# Sheet1.net
KiCad netlist of a schematic drawn in Altium Designer
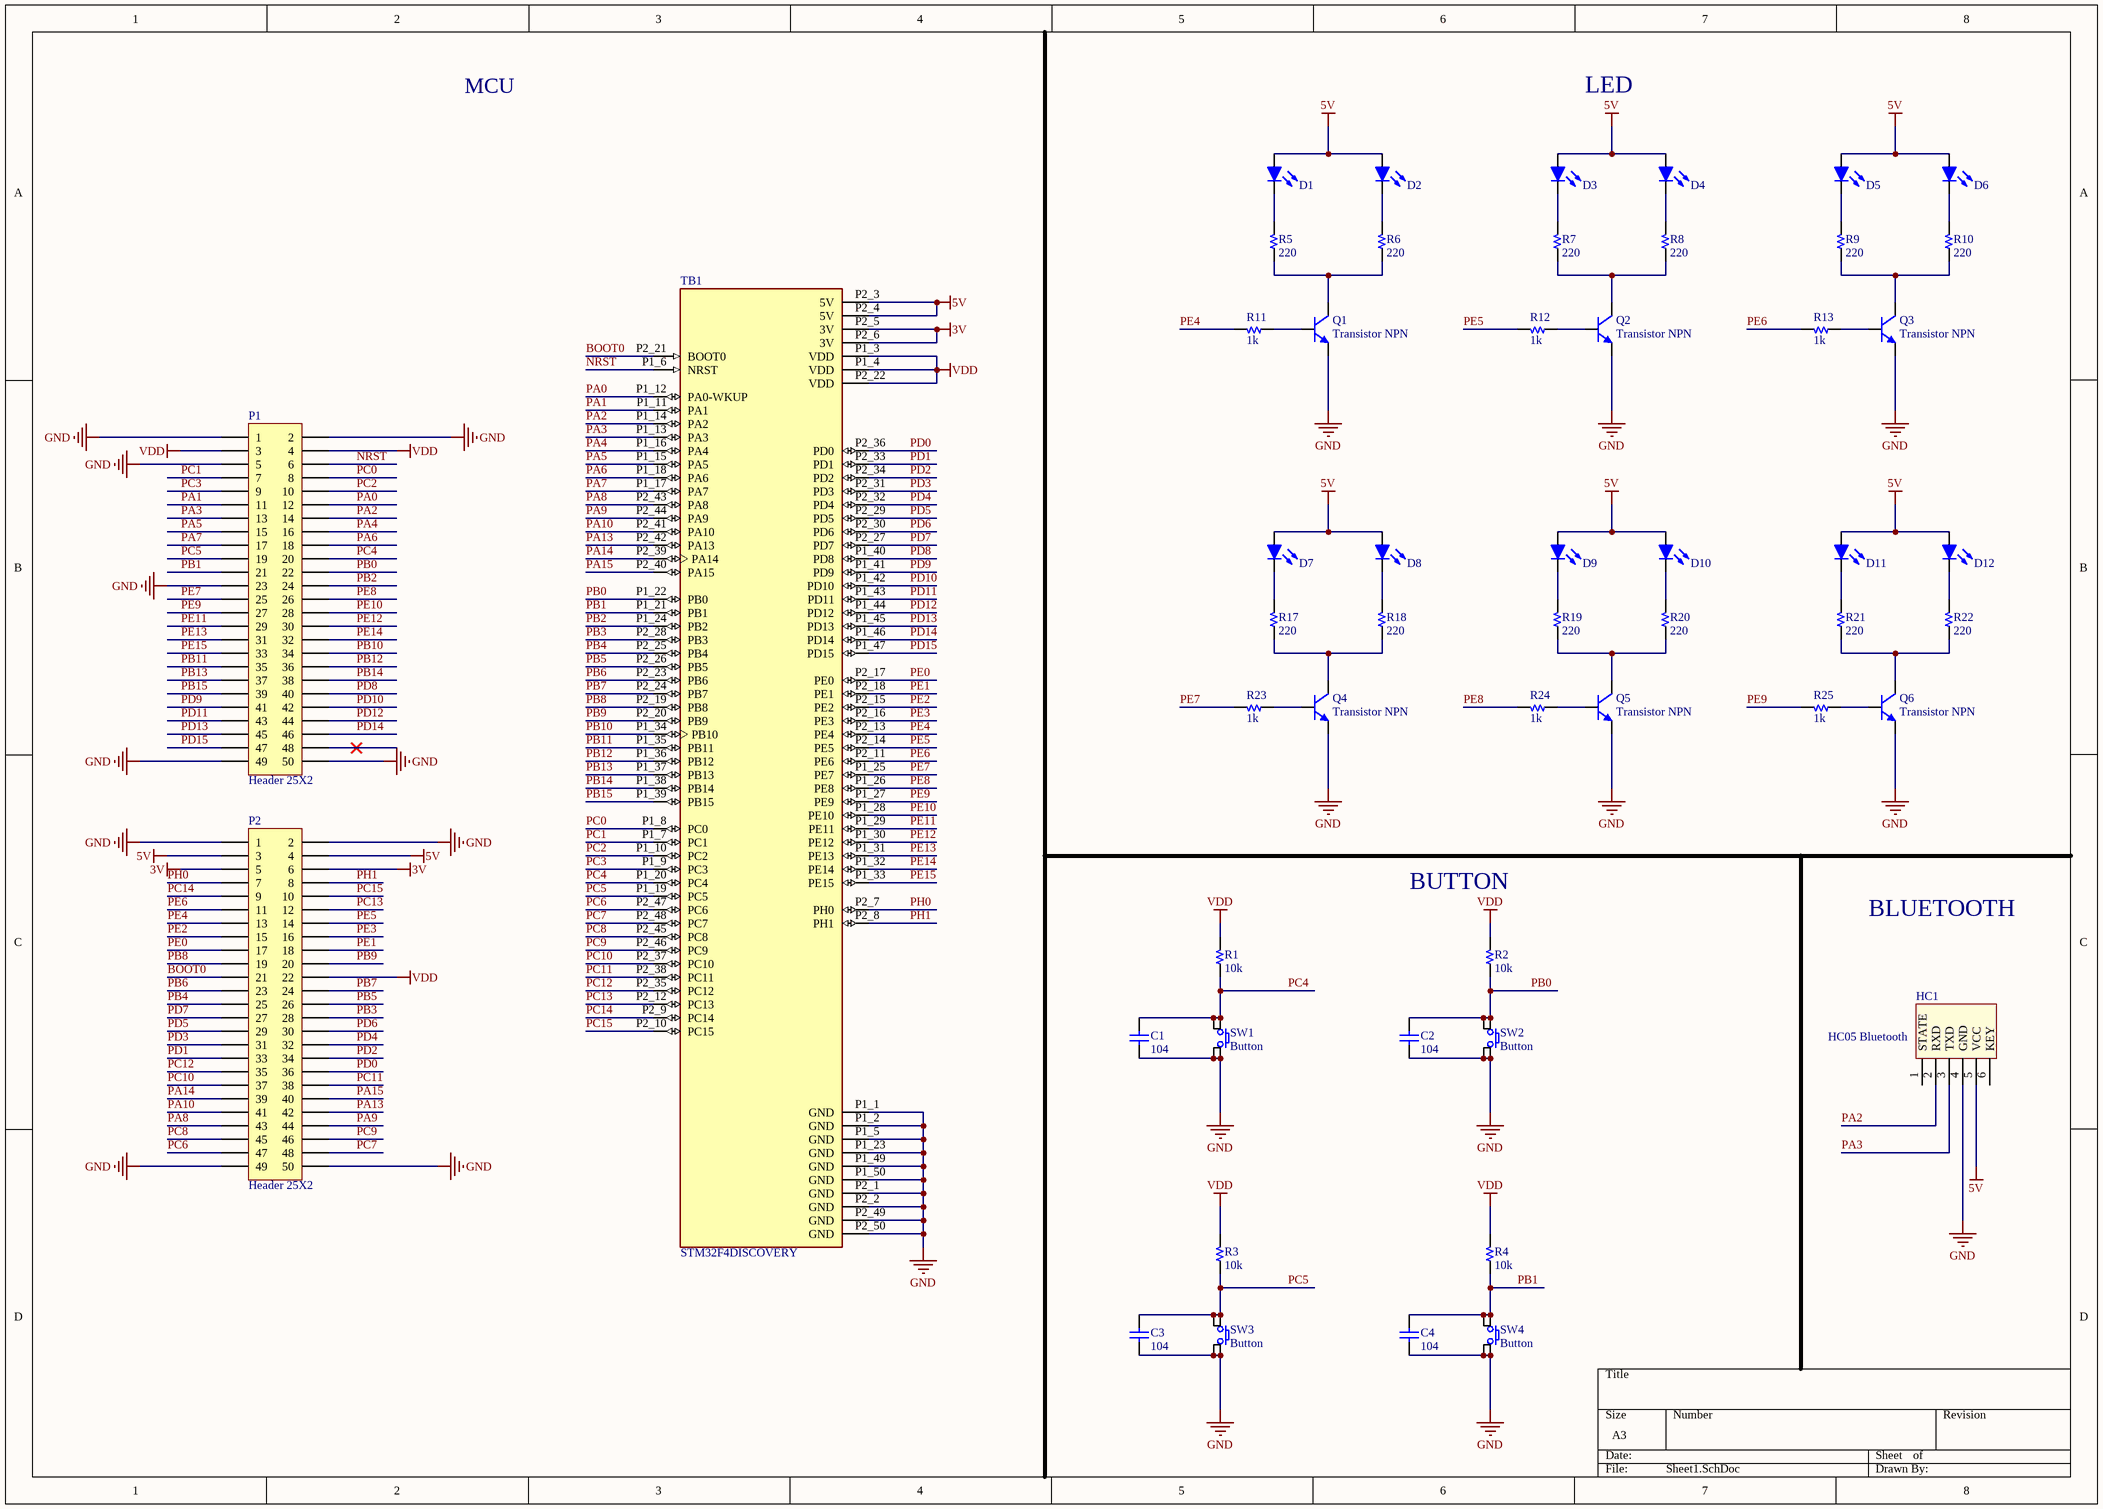
[diagram p0: Sheet1.SchDoc]

(export (version "E")
  (design (tool "Eeschema 10.0.6"))
  (components
    (comp (ref "C1")
      (value "104")
      (footprint "CAP Ceramic/W300")
      (description "Capacitor non-pol")
      (libsource (lib "chipfc_libs") (part "Capacitor NP"))
    )
    (comp (ref "C2")
      (value "104")
      (footprint "CAP Ceramic/W300")
      (description "Capacitor non-pol")
      (libsource (lib "chipfc_libs") (part "Capacitor NP"))
    )
    (comp (ref "C3")
      (value "104")
      (footprint "CAP Ceramic/W300")
      (description "Capacitor non-pol")
      (libsource (lib "chipfc_libs") (part "Capacitor NP"))
    )
    (comp (ref "C4")
      (value "104")
      (footprint "CAP Ceramic/W300")
      (description "Capacitor non-pol")
      (libsource (lib "chipfc_libs") (part "Capacitor NP"))
    )
    (comp (ref "D1")
      (value "Led")
      (footprint "LED 3MM - green")
      (description "Typical LED")
      (libsource (lib "led") (part "Led"))
    )
    (comp (ref "D2")
      (value "Led")
      (footprint "LED 3MM - green")
      (description "Typical LED")
      (libsource (lib "led") (part "Led"))
    )
    (comp (ref "D3")
      (value "Led")
      (footprint "LED 3MM - yellow")
      (description "Typical LED")
      (libsource (lib "led") (part "Led"))
    )
    (comp (ref "D4")
      (value "Led")
      (footprint "LED 3MM - yellow")
      (description "Typical LED")
      (libsource (lib "led") (part "Led"))
    )
    (comp (ref "D5")
      (value "Led")
      (footprint "LED 3MM - red")
      (description "Typical LED")
      (libsource (lib "led") (part "Led"))
    )
    (comp (ref "D6")
      (value "Led")
      (footprint "LED 3MM - red")
      (description "Typical LED")
      (libsource (lib "led") (part "Led"))
    )
    (comp (ref "D7")
      (value "Led")
      (footprint "LED 3MM - green")
      (description "Typical LED")
      (libsource (lib "led") (part "Led"))
    )
    (comp (ref "D8")
      (value "Led")
      (footprint "LED 3MM - green")
      (description "Typical LED")
      (libsource (lib "led") (part "Led"))
    )
    (comp (ref "D9")
      (value "Led")
      (footprint "LED 3MM - yellow")
      (description "Typical LED")
      (libsource (lib "led") (part "Led"))
    )
    (comp (ref "D10")
      (value "Led")
      (footprint "LED 3MM - yellow")
      (description "Typical LED")
      (libsource (lib "led") (part "Led"))
    )
    (comp (ref "D11")
      (value "Led")
      (footprint "LED 3MM - red")
      (description "Typical LED")
      (libsource (lib "led") (part "Led"))
    )
    (comp (ref "D12")
      (value "Led")
      (footprint "LED 3MM - red")
      (description "Typical LED")
      (libsource (lib "led") (part "Led"))
    )
    (comp (ref "HC1")
      (value "HC05 Bluetooth")
      (footprint "HC05 Bluethooth Dung")
      (description "Bluetooth HC05")
      (libsource (lib "Altium_Lib_by_KhueNguyenCreator") (part "HC05 Bluetooth"))
    )
    (comp (ref "P1")
      (value "Header 25X2")
      (footprint "HDR2X25")
      (description "Header, 25-Pin, Dual row")
      (fields (field (name "PUBLISHER") "Altium Limited"))
      (libsource (lib "Miscellaneous Connectors") (part "Header 25X2"))
    )
    (comp (ref "P2")
      (value "Header 25X2")
      (footprint "HDR2X25")
      (description "Header, 25-Pin, Dual row")
      (fields (field (name "PUBLISHER") "Altium Limited"))
      (libsource (lib "Miscellaneous Connectors") (part "Header 25X2"))
    )
    (comp (ref "Q1")
      (value "Transistor NPN")
      (footprint "TO-92/W100")
      (description "NPN Bipolar Transistor")
      (libsource (lib "chipfc_libs") (part "Transistor NPN"))
    )
    (comp (ref "Q2")
      (value "Transistor NPN")
      (footprint "TO-92/W100")
      (description "NPN Bipolar Transistor")
      (libsource (lib "chipfc_libs") (part "Transistor NPN"))
    )
    (comp (ref "Q3")
      (value "Transistor NPN")
      (footprint "TO-92/W100")
      (description "NPN Bipolar Transistor")
      (libsource (lib "chipfc_libs") (part "Transistor NPN"))
    )
    (comp (ref "Q4")
      (value "Transistor NPN")
      (footprint "TO-92/W100")
      (description "NPN Bipolar Transistor")
      (libsource (lib "chipfc_libs") (part "Transistor NPN"))
    )
    (comp (ref "Q5")
      (value "Transistor NPN")
      (footprint "TO-92/W100")
      (description "NPN Bipolar Transistor")
      (libsource (lib "chipfc_libs") (part "Transistor NPN"))
    )
    (comp (ref "Q6")
      (value "Transistor NPN")
      (footprint "TO-92/W100")
      (description "NPN Bipolar Transistor")
      (libsource (lib "chipfc_libs") (part "Transistor NPN"))
    )
    (comp (ref "R1")
      (value "10k")
      (footprint "R 1/4W/300")
      (description "Resistor")
      (libsource (lib "chipfc_libs") (part "Resistor"))
    )
    (comp (ref "R2")
      (value "10k")
      (footprint "R 1/4W/300")
      (description "Resistor")
      (libsource (lib "chipfc_libs") (part "Resistor"))
    )
    (comp (ref "R3")
      (value "10k")
      (footprint "R 1/4W/300")
      (description "Resistor")
      (libsource (lib "chipfc_libs") (part "Resistor"))
    )
    (comp (ref "R4")
      (value "10k")
      (footprint "R 1/4W/300")
      (description "Resistor")
      (libsource (lib "chipfc_libs") (part "Resistor"))
    )
    (comp (ref "R5")
      (value "220")
      (footprint "R 1/4W/300")
      (description "Resistor")
      (libsource (lib "chipfc_libs") (part "Resistor"))
    )
    (comp (ref "R6")
      (value "220")
      (footprint "R 1/4W/300")
      (description "Resistor")
      (libsource (lib "chipfc_libs") (part "Resistor"))
    )
    (comp (ref "R7")
      (value "220")
      (footprint "R 1/4W/300")
      (description "Resistor")
      (libsource (lib "chipfc_libs") (part "Resistor"))
    )
    (comp (ref "R8")
      (value "220")
      (footprint "R 1/4W/300")
      (description "Resistor")
      (libsource (lib "chipfc_libs") (part "Resistor"))
    )
    (comp (ref "R9")
      (value "220")
      (footprint "R 1/4W/300")
      (description "Resistor")
      (libsource (lib "chipfc_libs") (part "Resistor"))
    )
    (comp (ref "R10")
      (value "220")
      (footprint "R 1/4W/300")
      (description "Resistor")
      (libsource (lib "chipfc_libs") (part "Resistor"))
    )
    (comp (ref "R11")
      (value "1k")
      (footprint "R 1/4W/300")
      (description "Resistor")
      (libsource (lib "chipfc_libs") (part "Resistor"))
    )
    (comp (ref "R12")
      (value "1k")
      (footprint "R 1/4W/300")
      (description "Resistor")
      (libsource (lib "chipfc_libs") (part "Resistor"))
    )
    (comp (ref "R13")
      (value "1k")
      (footprint "R 1/4W/300")
      (description "Resistor")
      (libsource (lib "chipfc_libs") (part "Resistor"))
    )
    (comp (ref "R17")
      (value "220")
      (footprint "R 1/4W/300")
      (description "Resistor")
      (libsource (lib "chipfc_libs") (part "Resistor"))
    )
    (comp (ref "R18")
      (value "220")
      (footprint "R 1/4W/300")
      (description "Resistor")
      (libsource (lib "chipfc_libs") (part "Resistor"))
    )
    (comp (ref "R19")
      (value "220")
      (footprint "R 1/4W/300")
      (description "Resistor")
      (libsource (lib "chipfc_libs") (part "Resistor"))
    )
    (comp (ref "R20")
      (value "220")
      (footprint "R 1/4W/300")
      (description "Resistor")
      (libsource (lib "chipfc_libs") (part "Resistor"))
    )
    (comp (ref "R21")
      (value "220")
      (footprint "R 1/4W/300")
      (description "Resistor")
      (libsource (lib "chipfc_libs") (part "Resistor"))
    )
    (comp (ref "R22")
      (value "220")
      (footprint "R 1/4W/300")
      (description "Resistor")
      (libsource (lib "chipfc_libs") (part "Resistor"))
    )
    (comp (ref "R23")
      (value "1k")
      (footprint "R 1/4W/300")
      (description "Resistor")
      (libsource (lib "chipfc_libs") (part "Resistor"))
    )
    (comp (ref "R24")
      (value "1k")
      (footprint "R 1/4W/300")
      (description "Resistor")
      (libsource (lib "chipfc_libs") (part "Resistor"))
    )
    (comp (ref "R25")
      (value "1k")
      (footprint "R 1/4W/300")
      (description "Resistor")
      (libsource (lib "chipfc_libs") (part "Resistor"))
    )
    (comp (ref "SW1")
      (value "Button")
      (footprint "SW/4/12mm")
      (description "Tact switch 4-pin")
      (libsource (lib "bs_libs") (part "SW SPST 4-pin"))
    )
    (comp (ref "SW2")
      (value "Button")
      (footprint "SW/4/12mm")
      (description "Tact switch 4-pin")
      (libsource (lib "bs_libs") (part "SW SPST 4-pin"))
    )
    (comp (ref "SW3")
      (value "Button")
      (footprint "SW/4/12mm")
      (description "Tact switch 4-pin")
      (libsource (lib "bs_libs") (part "SW SPST 4-pin"))
    )
    (comp (ref "SW4")
      (value "Button")
      (footprint "SW/4/12mm")
      (description "Tact switch 4-pin")
      (libsource (lib "bs_libs") (part "SW SPST 4-pin"))
    )
    (comp (ref "TB1")
      (value "STM32F4DISCOVERY")
      (footprint "MODULE_STM32F4DISCOVERY")
      (description "Development kit: ARM ST; pin strips, pin header; No.of")
      (libsource (lib "STM32F4DISCOVERY") (part "STM32F4DISCOVERY"))
    )
  )
  (nets
    (net (code "1") (name "/BOOT0") (class "Default")
      (node (ref "P2") (pin "21") (pinfunction "21_21") (pintype "passive"))
      (node (ref "TB1") (pin "P2_21") (pinfunction "BOOT0_P2_21") (pintype "input"))
    )
    (net (code "2") (name "/NRST") (class "Default")
      (node (ref "P1") (pin "6") (pinfunction "6_6") (pintype "passive"))
      (node (ref "TB1") (pin "P1_6") (pinfunction "NRST_P1_6") (pintype "input"))
    )
    (net (code "3") (name "/PA0") (class "Default")
      (node (ref "P1") (pin "12") (pinfunction "12_12") (pintype "passive"))
      (node (ref "TB1") (pin "P1_12") (pinfunction "PA0-WKUP_P1_12") (pintype "bidirectional"))
    )
    (net (code "4") (name "/PA1") (class "Default")
      (node (ref "P1") (pin "11") (pinfunction "11_11") (pintype "passive"))
      (node (ref "TB1") (pin "P1_11") (pinfunction "PA1_P1_11") (pintype "bidirectional"))
    )
    (net (code "5") (name "/PA2") (class "Default")
      (node (ref "HC1") (pin "2") (pinfunction "RXD_2") (pintype "passive"))
      (node (ref "P1") (pin "14") (pinfunction "14_14") (pintype "passive"))
      (node (ref "TB1") (pin "P1_14") (pinfunction "PA2_P1_14") (pintype "bidirectional"))
    )
    (net (code "6") (name "/PA3") (class "Default")
      (node (ref "HC1") (pin "3") (pinfunction "TXD_3") (pintype "passive"))
      (node (ref "P1") (pin "13") (pinfunction "13_13") (pintype "passive"))
      (node (ref "TB1") (pin "P1_13") (pinfunction "PA3_P1_13") (pintype "bidirectional"))
    )
    (net (code "7") (name "/PA4") (class "Default")
      (node (ref "P1") (pin "16") (pinfunction "16_16") (pintype "passive"))
      (node (ref "TB1") (pin "P1_16") (pinfunction "PA4_P1_16") (pintype "bidirectional"))
    )
    (net (code "8") (name "/PA5") (class "Default")
      (node (ref "P1") (pin "15") (pinfunction "15_15") (pintype "passive"))
      (node (ref "TB1") (pin "P1_15") (pinfunction "PA5_P1_15") (pintype "bidirectional"))
    )
    (net (code "9") (name "/PA6") (class "Default")
      (node (ref "P1") (pin "18") (pinfunction "18_18") (pintype "passive"))
      (node (ref "TB1") (pin "P1_18") (pinfunction "PA6_P1_18") (pintype "bidirectional"))
    )
    (net (code "10") (name "/PA7") (class "Default")
      (node (ref "P1") (pin "17") (pinfunction "17_17") (pintype "passive"))
      (node (ref "TB1") (pin "P1_17") (pinfunction "PA7_P1_17") (pintype "bidirectional"))
    )
    (net (code "11") (name "/PA8") (class "Default")
      (node (ref "P2") (pin "43") (pinfunction "43_43") (pintype "passive"))
      (node (ref "TB1") (pin "P2_43") (pinfunction "PA8_P2_43") (pintype "bidirectional"))
    )
    (net (code "12") (name "/PA9") (class "Default")
      (node (ref "P2") (pin "44") (pinfunction "44_44") (pintype "passive"))
      (node (ref "TB1") (pin "P2_44") (pinfunction "PA9_P2_44") (pintype "bidirectional"))
    )
    (net (code "13") (name "/PA10") (class "Default")
      (node (ref "P2") (pin "41") (pinfunction "41_41") (pintype "passive"))
      (node (ref "TB1") (pin "P2_41") (pinfunction "PA10_P2_41") (pintype "bidirectional"))
    )
    (net (code "14") (name "/PA13") (class "Default")
      (node (ref "P2") (pin "42") (pinfunction "42_42") (pintype "passive"))
      (node (ref "TB1") (pin "P2_42") (pinfunction "PA13_P2_42") (pintype "bidirectional"))
    )
    (net (code "15") (name "/PA14") (class "Default")
      (node (ref "P2") (pin "39") (pinfunction "39_39") (pintype "passive"))
      (node (ref "TB1") (pin "P2_39") (pinfunction "PA14_P2_39") (pintype "bidirectional"))
    )
    (net (code "16") (name "/PA15") (class "Default")
      (node (ref "P2") (pin "40") (pinfunction "40_40") (pintype "passive"))
      (node (ref "TB1") (pin "P2_40") (pinfunction "PA15_P2_40") (pintype "bidirectional"))
    )
    (net (code "17") (name "/PB0") (class "Default")
      (node (ref "C2") (pin "1") (pinfunction "1_1") (pintype "passive"))
      (node (ref "P1") (pin "22") (pinfunction "22_22") (pintype "passive"))
      (node (ref "R2") (pin "1") (pinfunction "1_1") (pintype "passive"))
      (node (ref "SW2") (pin "1") (pinfunction "1_1") (pintype "passive"))
      (node (ref "SW2") (pin "2") (pinfunction "2_2") (pintype "passive"))
      (node (ref "TB1") (pin "P1_22") (pinfunction "PB0_P1_22") (pintype "bidirectional"))
    )
    (net (code "18") (name "/PB1") (class "Default")
      (node (ref "C4") (pin "1") (pinfunction "1_1") (pintype "passive"))
      (node (ref "P1") (pin "21") (pinfunction "21_21") (pintype "passive"))
      (node (ref "R4") (pin "1") (pinfunction "1_1") (pintype "passive"))
      (node (ref "SW4") (pin "1") (pinfunction "1_1") (pintype "passive"))
      (node (ref "SW4") (pin "2") (pinfunction "2_2") (pintype "passive"))
      (node (ref "TB1") (pin "P1_21") (pinfunction "PB1_P1_21") (pintype "bidirectional"))
    )
    (net (code "19") (name "/PB2") (class "Default")
      (node (ref "P1") (pin "24") (pinfunction "24_24") (pintype "passive"))
      (node (ref "TB1") (pin "P1_24") (pinfunction "PB2_P1_24") (pintype "bidirectional"))
    )
    (net (code "20") (name "/PB3") (class "Default")
      (node (ref "P2") (pin "28") (pinfunction "28_28") (pintype "passive"))
      (node (ref "TB1") (pin "P2_28") (pinfunction "PB3_P2_28") (pintype "bidirectional"))
    )
    (net (code "21") (name "/PB4") (class "Default")
      (node (ref "P2") (pin "25") (pinfunction "25_25") (pintype "passive"))
      (node (ref "TB1") (pin "P2_25") (pinfunction "PB4_P2_25") (pintype "bidirectional"))
    )
    (net (code "22") (name "/PB5") (class "Default")
      (node (ref "P2") (pin "26") (pinfunction "26_26") (pintype "passive"))
      (node (ref "TB1") (pin "P2_26") (pinfunction "PB5_P2_26") (pintype "bidirectional"))
    )
    (net (code "23") (name "/PB6") (class "Default")
      (node (ref "P2") (pin "23") (pinfunction "23_23") (pintype "passive"))
      (node (ref "TB1") (pin "P2_23") (pinfunction "PB6_P2_23") (pintype "bidirectional"))
    )
    (net (code "24") (name "/PB7") (class "Default")
      (node (ref "P2") (pin "24") (pinfunction "24_24") (pintype "passive"))
      (node (ref "TB1") (pin "P2_24") (pinfunction "PB7_P2_24") (pintype "bidirectional"))
    )
    (net (code "25") (name "/PB8") (class "Default")
      (node (ref "P2") (pin "19") (pinfunction "19_19") (pintype "passive"))
      (node (ref "TB1") (pin "P2_19") (pinfunction "PB8_P2_19") (pintype "bidirectional"))
    )
    (net (code "26") (name "/PB9") (class "Default")
      (node (ref "P2") (pin "20") (pinfunction "20_20") (pintype "passive"))
      (node (ref "TB1") (pin "P2_20") (pinfunction "PB9_P2_20") (pintype "bidirectional"))
    )
    (net (code "27") (name "/PB10") (class "Default")
      (node (ref "P1") (pin "34") (pinfunction "34_34") (pintype "passive"))
      (node (ref "TB1") (pin "P1_34") (pinfunction "PB10_P1_34") (pintype "bidirectional"))
    )
    (net (code "28") (name "/PB11") (class "Default")
      (node (ref "P1") (pin "35") (pinfunction "35_35") (pintype "passive"))
      (node (ref "TB1") (pin "P1_35") (pinfunction "PB11_P1_35") (pintype "bidirectional"))
    )
    (net (code "29") (name "/PB12") (class "Default")
      (node (ref "P1") (pin "36") (pinfunction "36_36") (pintype "passive"))
      (node (ref "TB1") (pin "P1_36") (pinfunction "PB12_P1_36") (pintype "bidirectional"))
    )
    (net (code "30") (name "/PB13") (class "Default")
      (node (ref "P1") (pin "37") (pinfunction "37_37") (pintype "passive"))
      (node (ref "TB1") (pin "P1_37") (pinfunction "PB13_P1_37") (pintype "bidirectional"))
    )
    (net (code "31") (name "/PB14") (class "Default")
      (node (ref "P1") (pin "38") (pinfunction "38_38") (pintype "passive"))
      (node (ref "TB1") (pin "P1_38") (pinfunction "PB14_P1_38") (pintype "bidirectional"))
    )
    (net (code "32") (name "/PB15") (class "Default")
      (node (ref "P1") (pin "39") (pinfunction "39_39") (pintype "passive"))
      (node (ref "TB1") (pin "P1_39") (pinfunction "PB15_P1_39") (pintype "bidirectional"))
    )
    (net (code "33") (name "/PC0") (class "Default")
      (node (ref "P1") (pin "8") (pinfunction "8_8") (pintype "passive"))
      (node (ref "TB1") (pin "P1_8") (pinfunction "PC0_P1_8") (pintype "bidirectional"))
    )
    (net (code "34") (name "/PC1") (class "Default")
      (node (ref "P1") (pin "7") (pinfunction "7_7") (pintype "passive"))
      (node (ref "TB1") (pin "P1_7") (pinfunction "PC1_P1_7") (pintype "bidirectional"))
    )
    (net (code "35") (name "/PC2") (class "Default")
      (node (ref "P1") (pin "10") (pinfunction "10_10") (pintype "passive"))
      (node (ref "TB1") (pin "P1_10") (pinfunction "PC2_P1_10") (pintype "bidirectional"))
    )
    (net (code "36") (name "/PC3") (class "Default")
      (node (ref "P1") (pin "9") (pinfunction "9_9") (pintype "passive"))
      (node (ref "TB1") (pin "P1_9") (pinfunction "PC3_P1_9") (pintype "bidirectional"))
    )
    (net (code "37") (name "/PC4") (class "Default")
      (node (ref "C1") (pin "1") (pinfunction "1_1") (pintype "passive"))
      (node (ref "P1") (pin "20") (pinfunction "20_20") (pintype "passive"))
      (node (ref "R1") (pin "1") (pinfunction "1_1") (pintype "passive"))
      (node (ref "SW1") (pin "1") (pinfunction "1_1") (pintype "passive"))
      (node (ref "SW1") (pin "2") (pinfunction "2_2") (pintype "passive"))
      (node (ref "TB1") (pin "P1_20") (pinfunction "PC4_P1_20") (pintype "bidirectional"))
    )
    (net (code "38") (name "/PC5") (class "Default")
      (node (ref "C3") (pin "1") (pinfunction "1_1") (pintype "passive"))
      (node (ref "P1") (pin "19") (pinfunction "19_19") (pintype "passive"))
      (node (ref "R3") (pin "1") (pinfunction "1_1") (pintype "passive"))
      (node (ref "SW3") (pin "1") (pinfunction "1_1") (pintype "passive"))
      (node (ref "SW3") (pin "2") (pinfunction "2_2") (pintype "passive"))
      (node (ref "TB1") (pin "P1_19") (pinfunction "PC5_P1_19") (pintype "bidirectional"))
    )
    (net (code "39") (name "/PC6") (class "Default")
      (node (ref "P2") (pin "47") (pinfunction "47_47") (pintype "passive"))
      (node (ref "TB1") (pin "P2_47") (pinfunction "PC6_P2_47") (pintype "bidirectional"))
    )
    (net (code "40") (name "/PC7") (class "Default")
      (node (ref "P2") (pin "48") (pinfunction "48_48") (pintype "passive"))
      (node (ref "TB1") (pin "P2_48") (pinfunction "PC7_P2_48") (pintype "bidirectional"))
    )
    (net (code "41") (name "/PC8") (class "Default")
      (node (ref "P2") (pin "45") (pinfunction "45_45") (pintype "passive"))
      (node (ref "TB1") (pin "P2_45") (pinfunction "PC8_P2_45") (pintype "bidirectional"))
    )
    (net (code "42") (name "/PC9") (class "Default")
      (node (ref "P2") (pin "46") (pinfunction "46_46") (pintype "passive"))
      (node (ref "TB1") (pin "P2_46") (pinfunction "PC9_P2_46") (pintype "bidirectional"))
    )
    (net (code "43") (name "/PC10") (class "Default")
      (node (ref "P2") (pin "37") (pinfunction "37_37") (pintype "passive"))
      (node (ref "TB1") (pin "P2_37") (pinfunction "PC10_P2_37") (pintype "bidirectional"))
    )
    (net (code "44") (name "/PC11") (class "Default")
      (node (ref "P2") (pin "38") (pinfunction "38_38") (pintype "passive"))
      (node (ref "TB1") (pin "P2_38") (pinfunction "PC11_P2_38") (pintype "bidirectional"))
    )
    (net (code "45") (name "/PC12") (class "Default")
      (node (ref "P2") (pin "35") (pinfunction "35_35") (pintype "passive"))
      (node (ref "TB1") (pin "P2_35") (pinfunction "PC12_P2_35") (pintype "bidirectional"))
    )
    (net (code "46") (name "/PC13") (class "Default")
      (node (ref "P2") (pin "12") (pinfunction "12_12") (pintype "passive"))
      (node (ref "TB1") (pin "P2_12") (pinfunction "PC13_P2_12") (pintype "bidirectional"))
    )
    (net (code "47") (name "/PC14") (class "Default")
      (node (ref "P2") (pin "9") (pinfunction "9_9") (pintype "passive"))
      (node (ref "TB1") (pin "P2_9") (pinfunction "PC14_P2_9") (pintype "bidirectional"))
    )
    (net (code "48") (name "/PC15") (class "Default")
      (node (ref "P2") (pin "10") (pinfunction "10_10") (pintype "passive"))
      (node (ref "TB1") (pin "P2_10") (pinfunction "PC15_P2_10") (pintype "bidirectional"))
    )
    (net (code "49") (name "/PD0") (class "Default")
      (node (ref "P2") (pin "36") (pinfunction "36_36") (pintype "passive"))
      (node (ref "TB1") (pin "P2_36") (pinfunction "PD0_P2_36") (pintype "bidirectional"))
    )
    (net (code "50") (name "/PD1") (class "Default")
      (node (ref "P2") (pin "33") (pinfunction "33_33") (pintype "passive"))
      (node (ref "TB1") (pin "P2_33") (pinfunction "PD1_P2_33") (pintype "bidirectional"))
    )
    (net (code "51") (name "/PD2") (class "Default")
      (node (ref "P2") (pin "34") (pinfunction "34_34") (pintype "passive"))
      (node (ref "TB1") (pin "P2_34") (pinfunction "PD2_P2_34") (pintype "bidirectional"))
    )
    (net (code "52") (name "/PD3") (class "Default")
      (node (ref "P2") (pin "31") (pinfunction "31_31") (pintype "passive"))
      (node (ref "TB1") (pin "P2_31") (pinfunction "PD3_P2_31") (pintype "bidirectional"))
    )
    (net (code "53") (name "/PD4") (class "Default")
      (node (ref "P2") (pin "32") (pinfunction "32_32") (pintype "passive"))
      (node (ref "TB1") (pin "P2_32") (pinfunction "PD4_P2_32") (pintype "bidirectional"))
    )
    (net (code "54") (name "/PD5") (class "Default")
      (node (ref "P2") (pin "29") (pinfunction "29_29") (pintype "passive"))
      (node (ref "TB1") (pin "P2_29") (pinfunction "PD5_P2_29") (pintype "bidirectional"))
    )
    (net (code "55") (name "/PD6") (class "Default")
      (node (ref "P2") (pin "30") (pinfunction "30_30") (pintype "passive"))
      (node (ref "TB1") (pin "P2_30") (pinfunction "PD6_P2_30") (pintype "bidirectional"))
    )
    (net (code "56") (name "/PD7") (class "Default")
      (node (ref "P2") (pin "27") (pinfunction "27_27") (pintype "passive"))
      (node (ref "TB1") (pin "P2_27") (pinfunction "PD7_P2_27") (pintype "bidirectional"))
    )
    (net (code "57") (name "/PD8") (class "Default")
      (node (ref "P1") (pin "40") (pinfunction "40_40") (pintype "passive"))
      (node (ref "TB1") (pin "P1_40") (pinfunction "PD8_P1_40") (pintype "bidirectional"))
    )
    (net (code "58") (name "/PD9") (class "Default")
      (node (ref "P1") (pin "41") (pinfunction "41_41") (pintype "passive"))
      (node (ref "TB1") (pin "P1_41") (pinfunction "PD9_P1_41") (pintype "bidirectional"))
    )
    (net (code "59") (name "/PD10") (class "Default")
      (node (ref "P1") (pin "42") (pinfunction "42_42") (pintype "passive"))
      (node (ref "TB1") (pin "P1_42") (pinfunction "PD10_P1_42") (pintype "bidirectional"))
    )
    (net (code "60") (name "/PD11") (class "Default")
      (node (ref "P1") (pin "43") (pinfunction "43_43") (pintype "passive"))
      (node (ref "TB1") (pin "P1_43") (pinfunction "PD11_P1_43") (pintype "bidirectional"))
    )
    (net (code "61") (name "/PD12") (class "Default")
      (node (ref "P1") (pin "44") (pinfunction "44_44") (pintype "passive"))
      (node (ref "TB1") (pin "P1_44") (pinfunction "PD12_P1_44") (pintype "bidirectional"))
    )
    (net (code "62") (name "/PD13") (class "Default")
      (node (ref "P1") (pin "45") (pinfunction "45_45") (pintype "passive"))
      (node (ref "TB1") (pin "P1_45") (pinfunction "PD13_P1_45") (pintype "bidirectional"))
    )
    (net (code "63") (name "/PD14") (class "Default")
      (node (ref "P1") (pin "46") (pinfunction "46_46") (pintype "passive"))
      (node (ref "TB1") (pin "P1_46") (pinfunction "PD14_P1_46") (pintype "bidirectional"))
    )
    (net (code "64") (name "/PD15") (class "Default")
      (node (ref "P1") (pin "47") (pinfunction "47_47") (pintype "passive"))
      (node (ref "TB1") (pin "P1_47") (pinfunction "PD15_P1_47") (pintype "bidirectional"))
    )
    (net (code "65") (name "/PE0") (class "Default")
      (node (ref "P2") (pin "17") (pinfunction "17_17") (pintype "passive"))
      (node (ref "TB1") (pin "P2_17") (pinfunction "PE0_P2_17") (pintype "bidirectional"))
    )
    (net (code "66") (name "/PE1") (class "Default")
      (node (ref "P2") (pin "18") (pinfunction "18_18") (pintype "passive"))
      (node (ref "TB1") (pin "P2_18") (pinfunction "PE1_P2_18") (pintype "bidirectional"))
    )
    (net (code "67") (name "/PE2") (class "Default")
      (node (ref "P2") (pin "15") (pinfunction "15_15") (pintype "passive"))
      (node (ref "TB1") (pin "P2_15") (pinfunction "PE2_P2_15") (pintype "bidirectional"))
    )
    (net (code "68") (name "/PE3") (class "Default")
      (node (ref "P2") (pin "16") (pinfunction "16_16") (pintype "passive"))
      (node (ref "TB1") (pin "P2_16") (pinfunction "PE3_P2_16") (pintype "bidirectional"))
    )
    (net (code "69") (name "/PE4") (class "Default")
      (node (ref "P2") (pin "13") (pinfunction "13_13") (pintype "passive"))
      (node (ref "R11") (pin "2") (pinfunction "2_2") (pintype "passive"))
      (node (ref "TB1") (pin "P2_13") (pinfunction "PE4_P2_13") (pintype "bidirectional"))
    )
    (net (code "70") (name "/PE5") (class "Default")
      (node (ref "P2") (pin "14") (pinfunction "14_14") (pintype "passive"))
      (node (ref "R12") (pin "2") (pinfunction "2_2") (pintype "passive"))
      (node (ref "TB1") (pin "P2_14") (pinfunction "PE5_P2_14") (pintype "bidirectional"))
    )
    (net (code "71") (name "/PE6") (class "Default")
      (node (ref "P2") (pin "11") (pinfunction "11_11") (pintype "passive"))
      (node (ref "R13") (pin "2") (pinfunction "2_2") (pintype "passive"))
      (node (ref "TB1") (pin "P2_11") (pinfunction "PE6_P2_11") (pintype "bidirectional"))
    )
    (net (code "72") (name "/PE7") (class "Default")
      (node (ref "P1") (pin "25") (pinfunction "25_25") (pintype "passive"))
      (node (ref "R23") (pin "2") (pinfunction "2_2") (pintype "passive"))
      (node (ref "TB1") (pin "P1_25") (pinfunction "PE7_P1_25") (pintype "bidirectional"))
    )
    (net (code "73") (name "/PE8") (class "Default")
      (node (ref "P1") (pin "26") (pinfunction "26_26") (pintype "passive"))
      (node (ref "R24") (pin "2") (pinfunction "2_2") (pintype "passive"))
      (node (ref "TB1") (pin "P1_26") (pinfunction "PE8_P1_26") (pintype "bidirectional"))
    )
    (net (code "74") (name "/PE9") (class "Default")
      (node (ref "P1") (pin "27") (pinfunction "27_27") (pintype "passive"))
      (node (ref "R25") (pin "2") (pinfunction "2_2") (pintype "passive"))
      (node (ref "TB1") (pin "P1_27") (pinfunction "PE9_P1_27") (pintype "bidirectional"))
    )
    (net (code "75") (name "/PE10") (class "Default")
      (node (ref "P1") (pin "28") (pinfunction "28_28") (pintype "passive"))
      (node (ref "TB1") (pin "P1_28") (pinfunction "PE10_P1_28") (pintype "bidirectional"))
    )
    (net (code "76") (name "/PE11") (class "Default")
      (node (ref "P1") (pin "29") (pinfunction "29_29") (pintype "passive"))
      (node (ref "TB1") (pin "P1_29") (pinfunction "PE11_P1_29") (pintype "bidirectional"))
    )
    (net (code "77") (name "/PE12") (class "Default")
      (node (ref "P1") (pin "30") (pinfunction "30_30") (pintype "passive"))
      (node (ref "TB1") (pin "P1_30") (pinfunction "PE12_P1_30") (pintype "bidirectional"))
    )
    (net (code "78") (name "/PE13") (class "Default")
      (node (ref "P1") (pin "31") (pinfunction "31_31") (pintype "passive"))
      (node (ref "TB1") (pin "P1_31") (pinfunction "PE13_P1_31") (pintype "bidirectional"))
    )
    (net (code "79") (name "/PE14") (class "Default")
      (node (ref "P1") (pin "32") (pinfunction "32_32") (pintype "passive"))
      (node (ref "TB1") (pin "P1_32") (pinfunction "PE14_P1_32") (pintype "bidirectional"))
    )
    (net (code "80") (name "/PE15") (class "Default")
      (node (ref "P1") (pin "33") (pinfunction "33_33") (pintype "passive"))
      (node (ref "TB1") (pin "P1_33") (pinfunction "PE15_P1_33") (pintype "bidirectional"))
    )
    (net (code "81") (name "/PH0") (class "Default")
      (node (ref "P2") (pin "7") (pinfunction "7_7") (pintype "passive"))
      (node (ref "TB1") (pin "P2_7") (pinfunction "PH0_P2_7") (pintype "bidirectional"))
    )
    (net (code "82") (name "/PH1") (class "Default")
      (node (ref "P2") (pin "8") (pinfunction "8_8") (pintype "passive"))
      (node (ref "TB1") (pin "P2_8") (pinfunction "PH1_P2_8") (pintype "bidirectional"))
    )
    (net (code "83") (name "3V") (class "Default")
      (node (ref "P2") (pin "5") (pinfunction "5_5") (pintype "passive"))
      (node (ref "P2") (pin "6") (pinfunction "6_6") (pintype "passive"))
      (node (ref "TB1") (pin "P2_5") (pinfunction "3V_P2_5") (pintype "power_in"))
      (node (ref "TB1") (pin "P2_6") (pinfunction "3V_P2_6") (pintype "power_in"))
    )
    (net (code "84") (name "5V") (class "Default")
      (node (ref "D1") (pin "1") (pinfunction "A_1") (pintype "passive"))
      (node (ref "D10") (pin "1") (pinfunction "A_1") (pintype "passive"))
      (node (ref "D11") (pin "1") (pinfunction "A_1") (pintype "passive"))
      (node (ref "D12") (pin "1") (pinfunction "A_1") (pintype "passive"))
      (node (ref "D2") (pin "1") (pinfunction "A_1") (pintype "passive"))
      (node (ref "D3") (pin "1") (pinfunction "A_1") (pintype "passive"))
      (node (ref "D4") (pin "1") (pinfunction "A_1") (pintype "passive"))
      (node (ref "D5") (pin "1") (pinfunction "A_1") (pintype "passive"))
      (node (ref "D6") (pin "1") (pinfunction "A_1") (pintype "passive"))
      (node (ref "D7") (pin "1") (pinfunction "A_1") (pintype "passive"))
      (node (ref "D8") (pin "1") (pinfunction "A_1") (pintype "passive"))
      (node (ref "D9") (pin "1") (pinfunction "A_1") (pintype "passive"))
      (node (ref "HC1") (pin "5") (pinfunction "VCC_5") (pintype "passive"))
      (node (ref "P2") (pin "3") (pinfunction "3_3") (pintype "passive"))
      (node (ref "P2") (pin "4") (pinfunction "4_4") (pintype "passive"))
      (node (ref "TB1") (pin "P2_3") (pinfunction "5V_P2_3") (pintype "power_in"))
      (node (ref "TB1") (pin "P2_4") (pinfunction "5V_P2_4") (pintype "power_in"))
    )
    (net (code "85") (name "GND") (class "Default")
      (node (ref "C1") (pin "2") (pinfunction "2_2") (pintype "passive"))
      (node (ref "C2") (pin "2") (pinfunction "2_2") (pintype "passive"))
      (node (ref "C3") (pin "2") (pinfunction "2_2") (pintype "passive"))
      (node (ref "C4") (pin "2") (pinfunction "2_2") (pintype "passive"))
      (node (ref "HC1") (pin "4") (pinfunction "GND_4") (pintype "passive"))
      (node (ref "P1") (pin "1") (pinfunction "1_1") (pintype "passive"))
      (node (ref "P1") (pin "2") (pinfunction "2_2") (pintype "passive"))
      (node (ref "P1") (pin "23") (pinfunction "23_23") (pintype "passive"))
      (node (ref "P1") (pin "49") (pinfunction "49_49") (pintype "passive"))
      (node (ref "P1") (pin "5") (pinfunction "5_5") (pintype "passive"))
      (node (ref "P1") (pin "50") (pinfunction "50_50") (pintype "passive"))
      (node (ref "P2") (pin "1") (pinfunction "1_1") (pintype "passive"))
      (node (ref "P2") (pin "2") (pinfunction "2_2") (pintype "passive"))
      (node (ref "P2") (pin "49") (pinfunction "49_49") (pintype "passive"))
      (node (ref "P2") (pin "50") (pinfunction "50_50") (pintype "passive"))
      (node (ref "Q1") (pin "2") (pinfunction "E_2") (pintype "passive"))
      (node (ref "Q2") (pin "2") (pinfunction "E_2") (pintype "passive"))
      (node (ref "Q3") (pin "2") (pinfunction "E_2") (pintype "passive"))
      (node (ref "Q4") (pin "2") (pinfunction "E_2") (pintype "passive"))
      (node (ref "Q5") (pin "2") (pinfunction "E_2") (pintype "passive"))
      (node (ref "Q6") (pin "2") (pinfunction "E_2") (pintype "passive"))
      (node (ref "SW1") (pin "3") (pinfunction "3_3") (pintype "passive"))
      (node (ref "SW1") (pin "4") (pinfunction "4_4") (pintype "passive"))
      (node (ref "SW2") (pin "3") (pinfunction "3_3") (pintype "passive"))
      (node (ref "SW2") (pin "4") (pinfunction "4_4") (pintype "passive"))
      (node (ref "SW3") (pin "3") (pinfunction "3_3") (pintype "passive"))
      (node (ref "SW3") (pin "4") (pinfunction "4_4") (pintype "passive"))
      (node (ref "SW4") (pin "3") (pinfunction "3_3") (pintype "passive"))
      (node (ref "SW4") (pin "4") (pinfunction "4_4") (pintype "passive"))
      (node (ref "TB1") (pin "P1_1") (pinfunction "GND_P1_1") (pintype "power_in"))
      (node (ref "TB1") (pin "P1_2") (pinfunction "GND_P1_2") (pintype "power_in"))
      (node (ref "TB1") (pin "P1_23") (pinfunction "GND_P1_23") (pintype "power_in"))
      (node (ref "TB1") (pin "P1_49") (pinfunction "GND_P1_49") (pintype "power_in"))
      (node (ref "TB1") (pin "P1_5") (pinfunction "GND_P1_5") (pintype "power_in"))
      (node (ref "TB1") (pin "P1_50") (pinfunction "GND_P1_50") (pintype "power_in"))
      (node (ref "TB1") (pin "P2_1") (pinfunction "GND_P2_1") (pintype "power_in"))
      (node (ref "TB1") (pin "P2_2") (pinfunction "GND_P2_2") (pintype "power_in"))
      (node (ref "TB1") (pin "P2_49") (pinfunction "GND_P2_49") (pintype "power_in"))
      (node (ref "TB1") (pin "P2_50") (pinfunction "GND_P2_50") (pintype "power_in"))
    )
    (net (code "86") (name "Net-(D1-K)") (class "Default")
      (node (ref "D1") (pin "2") (pinfunction "K_2") (pintype "passive"))
      (node (ref "R5") (pin "2") (pinfunction "2_2") (pintype "passive"))
    )
    (net (code "87") (name "Net-(D2-K)") (class "Default")
      (node (ref "D2") (pin "2") (pinfunction "K_2") (pintype "passive"))
      (node (ref "R6") (pin "2") (pinfunction "2_2") (pintype "passive"))
    )
    (net (code "88") (name "Net-(D3-K)") (class "Default")
      (node (ref "D3") (pin "2") (pinfunction "K_2") (pintype "passive"))
      (node (ref "R7") (pin "2") (pinfunction "2_2") (pintype "passive"))
    )
    (net (code "89") (name "Net-(D4-K)") (class "Default")
      (node (ref "D4") (pin "2") (pinfunction "K_2") (pintype "passive"))
      (node (ref "R8") (pin "2") (pinfunction "2_2") (pintype "passive"))
    )
    (net (code "90") (name "Net-(D5-K)") (class "Default")
      (node (ref "D5") (pin "2") (pinfunction "K_2") (pintype "passive"))
      (node (ref "R9") (pin "2") (pinfunction "2_2") (pintype "passive"))
    )
    (net (code "91") (name "Net-(D6-K)") (class "Default")
      (node (ref "D6") (pin "2") (pinfunction "K_2") (pintype "passive"))
      (node (ref "R10") (pin "2") (pinfunction "2_2") (pintype "passive"))
    )
    (net (code "92") (name "Net-(D7-K)") (class "Default")
      (node (ref "D7") (pin "2") (pinfunction "K_2") (pintype "passive"))
      (node (ref "R17") (pin "2") (pinfunction "2_2") (pintype "passive"))
    )
    (net (code "93") (name "Net-(D8-K)") (class "Default")
      (node (ref "D8") (pin "2") (pinfunction "K_2") (pintype "passive"))
      (node (ref "R18") (pin "2") (pinfunction "2_2") (pintype "passive"))
    )
    (net (code "94") (name "Net-(D9-K)") (class "Default")
      (node (ref "D9") (pin "2") (pinfunction "K_2") (pintype "passive"))
      (node (ref "R19") (pin "2") (pinfunction "2_2") (pintype "passive"))
    )
    (net (code "95") (name "Net-(D10-K)") (class "Default")
      (node (ref "D10") (pin "2") (pinfunction "K_2") (pintype "passive"))
      (node (ref "R20") (pin "2") (pinfunction "2_2") (pintype "passive"))
    )
    (net (code "96") (name "Net-(D11-K)") (class "Default")
      (node (ref "D11") (pin "2") (pinfunction "K_2") (pintype "passive"))
      (node (ref "R21") (pin "2") (pinfunction "2_2") (pintype "passive"))
    )
    (net (code "97") (name "Net-(D12-K)") (class "Default")
      (node (ref "D12") (pin "2") (pinfunction "K_2") (pintype "passive"))
      (node (ref "R22") (pin "2") (pinfunction "2_2") (pintype "passive"))
    )
    (net (code "98") (name "Net-(Q1-B)") (class "Default")
      (node (ref "Q1") (pin "1") (pinfunction "B_1") (pintype "passive"))
      (node (ref "R11") (pin "1") (pinfunction "1_1") (pintype "passive"))
    )
    (net (code "99") (name "Net-(Q1-C)") (class "Default")
      (node (ref "Q1") (pin "3") (pinfunction "C_3") (pintype "passive"))
      (node (ref "R5") (pin "1") (pinfunction "1_1") (pintype "passive"))
      (node (ref "R6") (pin "1") (pinfunction "1_1") (pintype "passive"))
    )
    (net (code "100") (name "Net-(Q2-B)") (class "Default")
      (node (ref "Q2") (pin "1") (pinfunction "B_1") (pintype "passive"))
      (node (ref "R12") (pin "1") (pinfunction "1_1") (pintype "passive"))
    )
    (net (code "101") (name "Net-(Q2-C)") (class "Default")
      (node (ref "Q2") (pin "3") (pinfunction "C_3") (pintype "passive"))
      (node (ref "R7") (pin "1") (pinfunction "1_1") (pintype "passive"))
      (node (ref "R8") (pin "1") (pinfunction "1_1") (pintype "passive"))
    )
    (net (code "102") (name "Net-(Q3-B)") (class "Default")
      (node (ref "Q3") (pin "1") (pinfunction "B_1") (pintype "passive"))
      (node (ref "R13") (pin "1") (pinfunction "1_1") (pintype "passive"))
    )
    (net (code "103") (name "Net-(Q3-C)") (class "Default")
      (node (ref "Q3") (pin "3") (pinfunction "C_3") (pintype "passive"))
      (node (ref "R10") (pin "1") (pinfunction "1_1") (pintype "passive"))
      (node (ref "R9") (pin "1") (pinfunction "1_1") (pintype "passive"))
    )
    (net (code "104") (name "Net-(Q4-B)") (class "Default")
      (node (ref "Q4") (pin "1") (pinfunction "B_1") (pintype "passive"))
      (node (ref "R23") (pin "1") (pinfunction "1_1") (pintype "passive"))
    )
    (net (code "105") (name "Net-(Q4-C)") (class "Default")
      (node (ref "Q4") (pin "3") (pinfunction "C_3") (pintype "passive"))
      (node (ref "R17") (pin "1") (pinfunction "1_1") (pintype "passive"))
      (node (ref "R18") (pin "1") (pinfunction "1_1") (pintype "passive"))
    )
    (net (code "106") (name "Net-(Q5-B)") (class "Default")
      (node (ref "Q5") (pin "1") (pinfunction "B_1") (pintype "passive"))
      (node (ref "R24") (pin "1") (pinfunction "1_1") (pintype "passive"))
    )
    (net (code "107") (name "Net-(Q5-C)") (class "Default")
      (node (ref "Q5") (pin "3") (pinfunction "C_3") (pintype "passive"))
      (node (ref "R19") (pin "1") (pinfunction "1_1") (pintype "passive"))
      (node (ref "R20") (pin "1") (pinfunction "1_1") (pintype "passive"))
    )
    (net (code "108") (name "Net-(Q6-B)") (class "Default")
      (node (ref "Q6") (pin "1") (pinfunction "B_1") (pintype "passive"))
      (node (ref "R25") (pin "1") (pinfunction "1_1") (pintype "passive"))
    )
    (net (code "109") (name "Net-(Q6-C)") (class "Default")
      (node (ref "Q6") (pin "3") (pinfunction "C_3") (pintype "passive"))
      (node (ref "R21") (pin "1") (pinfunction "1_1") (pintype "passive"))
      (node (ref "R22") (pin "1") (pinfunction "1_1") (pintype "passive"))
    )
    (net (code "110") (name "VDD") (class "Default")
      (node (ref "P1") (pin "3") (pinfunction "3_3") (pintype "passive"))
      (node (ref "P1") (pin "4") (pinfunction "4_4") (pintype "passive"))
      (node (ref "P2") (pin "22") (pinfunction "22_22") (pintype "passive"))
      (node (ref "R1") (pin "2") (pinfunction "2_2") (pintype "passive"))
      (node (ref "R2") (pin "2") (pinfunction "2_2") (pintype "passive"))
      (node (ref "R3") (pin "2") (pinfunction "2_2") (pintype "passive"))
      (node (ref "R4") (pin "2") (pinfunction "2_2") (pintype "passive"))
      (node (ref "TB1") (pin "P1_3") (pinfunction "VDD_P1_3") (pintype "power_in"))
      (node (ref "TB1") (pin "P1_4") (pinfunction "VDD_P1_4") (pintype "power_in"))
      (node (ref "TB1") (pin "P2_22") (pinfunction "VDD_P2_22") (pintype "power_in"))
    )
    (net (code "111") (name "unconnected-(HC1-KEY-Pad6)") (class "Default")
      (node (ref "HC1") (pin "6") (pinfunction "KEY_6") (pintype "passive"))
    )
    (net (code "112") (name "unconnected-(HC1-STATE-Pad1)") (class "Default")
      (node (ref "HC1") (pin "1") (pinfunction "STATE_1") (pintype "passive"))
    )
    (net (code "113") (name "unconnected-(P1-Pad48)") (class "Default")
      (node (ref "P1") (pin "48") (pinfunction "48_48") (pintype "passive"))
    )
  )
)
